# fsk_schematic.net
KiCad netlist of a schematic drawn in EAGLE
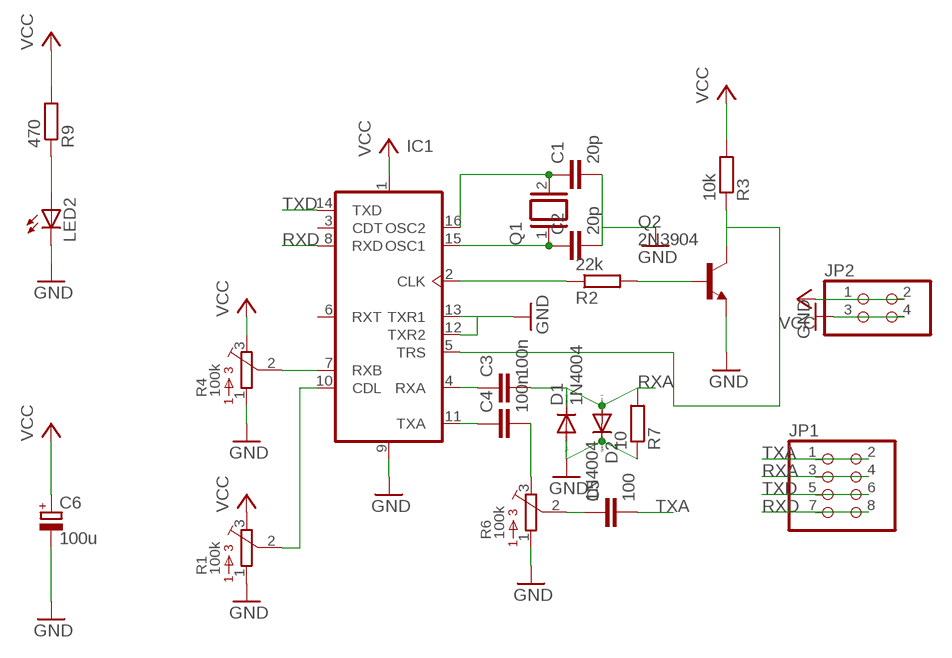
[diagram p0: schematic, sheet 1]

(export (version "E")
  (design (tool "Eeschema 10.0.6"))
  (components
    (comp (ref "C1")
      (value "20p")
      (footprint "eagle-import:C025-024X044")
      (libsource (lib "eagle-import") (part "C-EU025-024X044"))
    )
    (comp (ref "C2")
      (value "20p")
      (footprint "eagle-import:C025-024X044")
      (libsource (lib "eagle-import") (part "C-EU025-024X044"))
    )
    (comp (ref "C3")
      (value "100n")
      (footprint "eagle-import:C050-045X075")
      (libsource (lib "eagle-import") (part "C-EU050-045X075"))
    )
    (comp (ref "C4")
      (value "100n")
      (footprint "eagle-import:C050-045X075")
      (libsource (lib "eagle-import") (part "C-EU050-045X075"))
    )
    (comp (ref "C5")
      (value "100")
      (footprint "eagle-import:C050-045X075")
      (libsource (lib "eagle-import") (part "C-EU050-045X075"))
    )
    (comp (ref "C6")
      (value "100u")
      (footprint "eagle-import:E2,5-7")
      (libsource (lib "eagle-import") (part "CPOL-EUE2.5-7"))
    )
    (comp (ref "D1")
      (value "1N4004")
      (footprint "eagle-import:DO41-10")
      (libsource (lib "eagle-import") (part "1N4004"))
    )
    (comp (ref "D2")
      (value "1N4004")
      (footprint "eagle-import:DO41-10")
      (libsource (lib "eagle-import") (part "1N4004"))
    )
    (comp (ref "IC1")
      (value "TCM3105")
      (footprint "eagle-import:DIL16")
      (libsource (lib "eagle-import") (part "TCM3105"))
    )
    (comp (ref "JP1")
      (value "PINHD-2X4")
      (footprint "eagle-import:2X04")
      (libsource (lib "eagle-import") (part "PINHD-2X4"))
    )
    (comp (ref "JP2")
      (value "PINHD-2X2")
      (footprint "eagle-import:2X02")
      (libsource (lib "eagle-import") (part "PINHD-2X2"))
    )
    (comp (ref "LED2")
      (value "LED5MM")
      (footprint "eagle-import:LED5MM")
      (libsource (lib "eagle-import") (part "LED5MM"))
    )
    (comp (ref "Q1")
      (value "XTAL/S")
      (footprint "eagle-import:QS")
      (libsource (lib "eagle-import") (part "XTAL/S"))
    )
    (comp (ref "Q2")
      (value "2N3904")
      (footprint "eagle-import:TO92")
      (libsource (lib "eagle-import") (part "2N3904"))
    )
    (comp (ref "R1")
      (value "100k")
      (footprint "eagle-import:3386C")
      (libsource (lib "eagle-import") (part "3386-C"))
    )
    (comp (ref "R2")
      (value "22k")
      (footprint "eagle-import:0204_7")
      (libsource (lib "eagle-import") (part "R-EU_0204/7"))
    )
    (comp (ref "R3")
      (value "10k")
      (footprint "eagle-import:0204_7")
      (libsource (lib "eagle-import") (part "R-EU_0204/7"))
    )
    (comp (ref "R4")
      (value "100k")
      (footprint "eagle-import:3386C")
      (libsource (lib "eagle-import") (part "3386-C"))
    )
    (comp (ref "R6")
      (value "100k")
      (footprint "eagle-import:3386C")
      (libsource (lib "eagle-import") (part "3386-C"))
    )
    (comp (ref "R7")
      (value "10")
      (footprint "eagle-import:0204_7")
      (libsource (lib "eagle-import") (part "R-EU_0204/7"))
    )
    (comp (ref "R9")
      (value "470")
      (footprint "eagle-import:0204_7")
      (libsource (lib "eagle-import") (part "R-EU_0204/7"))
    )
  )
  (nets
    (net (code "1") (name "/RXA") (class "Default")
      (node (ref "C3") (pin "2") (pinfunction "2_2") (pintype "passive"))
      (node (ref "D1") (pin "C") (pinfunction "C_C") (pintype "passive"))
      (node (ref "D2") (pin "A") (pinfunction "A_A") (pintype "passive"))
      (node (ref "JP1") (pin "3") (pinfunction "3_3") (pintype "passive"))
      (node (ref "JP1") (pin "4") (pinfunction "4_4") (pintype "passive"))
      (node (ref "R7") (pin "2") (pinfunction "2_2") (pintype "passive"))
    )
    (net (code "2") (name "/RXD") (class "Default")
      (node (ref "IC1") (pin "8") (pinfunction "RXD_8") (pintype "output"))
      (node (ref "JP1") (pin "7") (pinfunction "7_7") (pintype "passive"))
      (node (ref "JP1") (pin "8") (pinfunction "8_8") (pintype "passive"))
    )
    (net (code "3") (name "/TXA") (class "Default")
      (node (ref "C5") (pin "2") (pinfunction "2_2") (pintype "passive"))
      (node (ref "JP1") (pin "1") (pinfunction "1_1") (pintype "passive"))
      (node (ref "JP1") (pin "2") (pinfunction "2_2") (pintype "passive"))
    )
    (net (code "4") (name "/TXD") (class "Default")
      (node (ref "IC1") (pin "14") (pinfunction "TXD_14") (pintype "input"))
      (node (ref "JP1") (pin "5") (pinfunction "5_5") (pintype "passive"))
      (node (ref "JP1") (pin "6") (pinfunction "6_6") (pintype "passive"))
    )
    (net (code "5") (name "GND") (class "Default")
      (node (ref "C1") (pin "2") (pinfunction "2_2") (pintype "passive"))
      (node (ref "C2") (pin "2") (pinfunction "2_2") (pintype "passive"))
      (node (ref "C6") (pin "-") (pinfunction "-_-") (pintype "passive"))
      (node (ref "D1") (pin "A") (pinfunction "A_A") (pintype "passive"))
      (node (ref "D2") (pin "C") (pinfunction "C_C") (pintype "passive"))
      (node (ref "IC1") (pin "12") (pinfunction "TXR2_12") (pintype "input"))
      (node (ref "IC1") (pin "13") (pinfunction "TXR1_13") (pintype "input"))
      (node (ref "IC1") (pin "9") (pinfunction "VSS_9") (pintype "power_in"))
      (node (ref "JP2") (pin "3") (pinfunction "3_3") (pintype "passive"))
      (node (ref "JP2") (pin "4") (pinfunction "4_4") (pintype "passive"))
      (node (ref "LED2") (pin "K") (pinfunction "C_K") (pintype "passive"))
      (node (ref "Q2") (pin "3") (pinfunction "E_3") (pintype "passive"))
      (node (ref "R1") (pin "1") (pinfunction "1_1") (pintype "passive"))
      (node (ref "R4") (pin "1") (pinfunction "1_1") (pintype "passive"))
      (node (ref "R6") (pin "1") (pinfunction "1_1") (pintype "passive"))
      (node (ref "R7") (pin "1") (pinfunction "1_1") (pintype "passive"))
    )
    (net (code "6") (name "Net-(C4-Pad2)") (class "Default")
      (node (ref "C4") (pin "2") (pinfunction "2_2") (pintype "passive"))
      (node (ref "R6") (pin "3") (pinfunction "3_3") (pintype "passive"))
    )
    (net (code "7") (name "Net-(C5-Pad1)") (class "Default")
      (node (ref "C5") (pin "1") (pinfunction "1_1") (pintype "passive"))
      (node (ref "R6") (pin "2") (pinfunction "2_2") (pintype "passive"))
    )
    (net (code "8") (name "Net-(IC1-CDL)") (class "Default")
      (node (ref "IC1") (pin "10") (pinfunction "CDL_10") (pintype "bidirectional"))
      (node (ref "R1") (pin "2") (pinfunction "2_2") (pintype "passive"))
    )
    (net (code "9") (name "Net-(IC1-CLK)") (class "Default")
      (node (ref "IC1") (pin "2") (pinfunction "CLK_2") (pintype "output"))
      (node (ref "R2") (pin "1") (pinfunction "1_1") (pintype "passive"))
    )
    (net (code "10") (name "Net-(IC1-OSC1)") (class "Default")
      (node (ref "C2") (pin "1") (pinfunction "1_1") (pintype "passive"))
      (node (ref "IC1") (pin "15") (pinfunction "OSC1_15") (pintype "bidirectional"))
      (node (ref "Q1") (pin "1") (pinfunction "1_1") (pintype "passive"))
    )
    (net (code "11") (name "Net-(IC1-OSC2)") (class "Default")
      (node (ref "C1") (pin "1") (pinfunction "1_1") (pintype "passive"))
      (node (ref "IC1") (pin "16") (pinfunction "OSC2_16") (pintype "bidirectional"))
      (node (ref "Q1") (pin "2") (pinfunction "2_2") (pintype "passive"))
    )
    (net (code "12") (name "Net-(IC1-RXA)") (class "Default")
      (node (ref "C3") (pin "1") (pinfunction "1_1") (pintype "passive"))
      (node (ref "IC1") (pin "4") (pinfunction "RXA_4") (pintype "input"))
    )
    (net (code "13") (name "Net-(IC1-RXB)") (class "Default")
      (node (ref "IC1") (pin "7") (pinfunction "RXB_7") (pintype "bidirectional"))
      (node (ref "R4") (pin "2") (pinfunction "2_2") (pintype "passive"))
    )
    (net (code "14") (name "Net-(IC1-TRS)") (class "Default")
      (node (ref "IC1") (pin "5") (pinfunction "TRS_5") (pintype "input"))
      (node (ref "Q2") (pin "1") (pinfunction "C_1") (pintype "passive"))
      (node (ref "R3") (pin "1") (pinfunction "1_1") (pintype "passive"))
    )
    (net (code "15") (name "Net-(IC1-TXA)") (class "Default")
      (node (ref "C4") (pin "1") (pinfunction "1_1") (pintype "passive"))
      (node (ref "IC1") (pin "11") (pinfunction "TXA_11") (pintype "output"))
    )
    (net (code "16") (name "Net-(LED2-PadA)") (class "Default")
      (node (ref "LED2") (pin "A") (pinfunction "A_A") (pintype "passive"))
      (node (ref "R9") (pin "1") (pinfunction "1_1") (pintype "passive"))
    )
    (net (code "17") (name "Net-(Q2-B)") (class "Default")
      (node (ref "Q2") (pin "2") (pinfunction "B_2") (pintype "passive"))
      (node (ref "R2") (pin "2") (pinfunction "2_2") (pintype "passive"))
    )
    (net (code "18") (name "VCC") (class "Default")
      (node (ref "C6") (pin "+") (pinfunction "+_+") (pintype "passive"))
      (node (ref "IC1") (pin "1") (pinfunction "VDD_1") (pintype "power_in"))
      (node (ref "JP2") (pin "1") (pinfunction "1_1") (pintype "passive"))
      (node (ref "JP2") (pin "2") (pinfunction "2_2") (pintype "passive"))
      (node (ref "R1") (pin "3") (pinfunction "3_3") (pintype "passive"))
      (node (ref "R3") (pin "2") (pinfunction "2_2") (pintype "passive"))
      (node (ref "R4") (pin "3") (pinfunction "3_3") (pintype "passive"))
      (node (ref "R9") (pin "2") (pinfunction "2_2") (pintype "passive"))
    )
    (net (code "19") (name "unconnected-(IC1-CDT-Pad3)") (class "Default")
      (node (ref "IC1") (pin "3") (pinfunction "CDT_3") (pintype "output"))
    )
    (net (code "20") (name "unconnected-(IC1-RXT-Pad6)") (class "Default")
      (node (ref "IC1") (pin "6") (pinfunction "RXT_6") (pintype "bidirectional"))
    )
  )
)
